# PIC32MX_circuit.net
KiCad netlist of a schematic drawn in Altium Designer
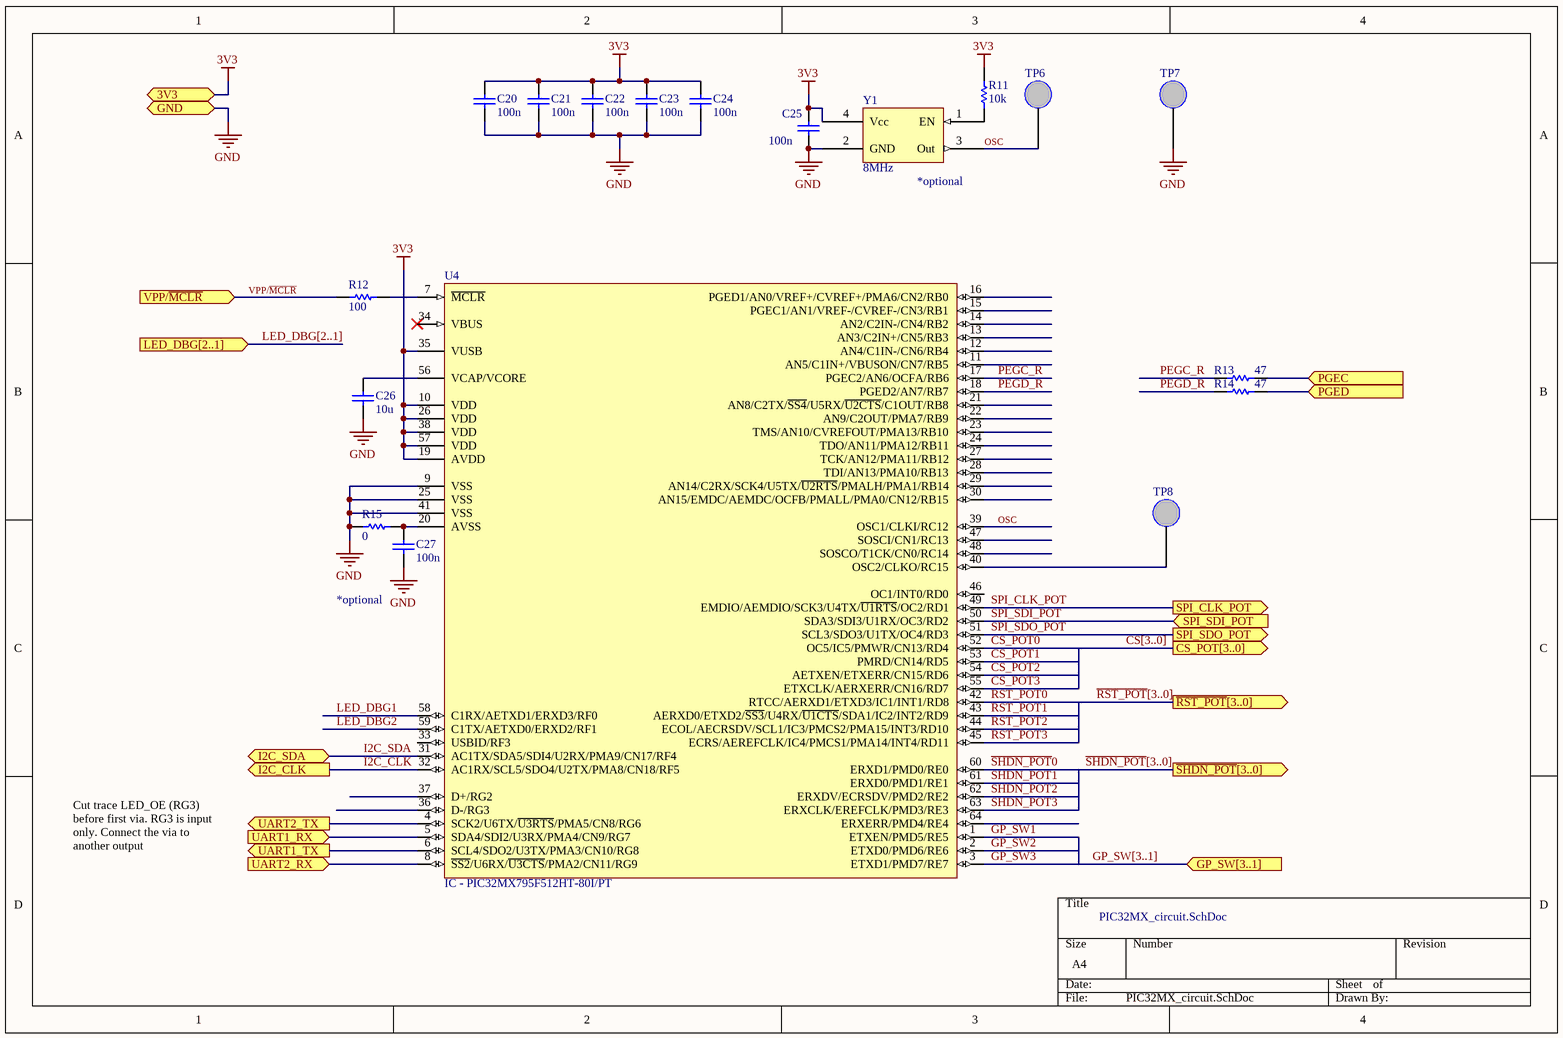
[diagram p0: PIC32MX_circuit.SchDoc]

(export (version "E")
  (design (tool "Eeschema 10.0.6"))
  (components
    (comp (ref "C20")
      (value "100n")
      (footprint "CS-0603")
      (fields
        (field (name "TOLERANCE") "10%")
        (field (name "VOLTAGE") "16V")
        (field (name "Comment") "CS - CAPACITOR")
      )
      (libsource (lib "CHINOOK_LIBRARY") (part "CS - CAPACITOR"))
    )
    (comp (ref "C21")
      (value "100n")
      (footprint "CS-0603")
      (fields
        (field (name "TOLERANCE") "10%")
        (field (name "VOLTAGE") "16V")
        (field (name "Comment") "CS - CAPACITOR")
      )
      (libsource (lib "CHINOOK_LIBRARY") (part "CS - CAPACITOR"))
    )
    (comp (ref "C22")
      (value "100n")
      (footprint "CS-0603")
      (fields
        (field (name "TOLERANCE") "10%")
        (field (name "VOLTAGE") "16V")
        (field (name "Comment") "CS - CAPACITOR")
      )
      (libsource (lib "CHINOOK_LIBRARY") (part "CS - CAPACITOR"))
    )
    (comp (ref "C23")
      (value "100n")
      (footprint "CS-0603")
      (fields
        (field (name "TOLERANCE") "10%")
        (field (name "VOLTAGE") "16V")
        (field (name "Comment") "CS - CAPACITOR")
      )
      (libsource (lib "CHINOOK_LIBRARY") (part "CS - CAPACITOR"))
    )
    (comp (ref "C24")
      (value "100n")
      (footprint "CS-0603")
      (fields
        (field (name "TOLERANCE") "10%")
        (field (name "VOLTAGE") "16V")
        (field (name "Comment") "CS - CAPACITOR")
      )
      (libsource (lib "CHINOOK_LIBRARY") (part "CS - CAPACITOR"))
    )
    (comp (ref "C25")
      (value "100n")
      (footprint "CS-0603")
      (fields
        (field (name "TOLERANCE") "10%")
        (field (name "VOLTAGE") "16V")
        (field (name "Comment") "CS - CAPACITOR")
      )
      (libsource (lib "CHINOOK_LIBRARY") (part "CS - CAPACITOR"))
    )
    (comp (ref "C26")
      (value "10u")
      (footprint "CS-0603")
      (fields
        (field (name "TOLERANCE") "10%")
        (field (name "VOLTAGE") "16V")
        (field (name "Comment") "CS - CAPACITOR")
      )
      (libsource (lib "CHINOOK_LIBRARY") (part "CS - CAPACITOR"))
    )
    (comp (ref "C27")
      (value "100n")
      (footprint "CS-0603")
      (fields
        (field (name "TOLERANCE") "10%")
        (field (name "VOLTAGE") "16V")
        (field (name "Comment") "CS - CAPACITOR")
      )
      (libsource (lib "CHINOOK_LIBRARY") (part "CS - CAPACITOR"))
    )
    (comp (ref "R11")
      (value "10k")
      (footprint "RS-0603")
      (fields
        (field (name "TOLERANCE") "RES TOL")
        (field (name "POWER") "RES POWER")
        (field (name "Comment") "RS - RESISTOR")
      )
      (libsource (lib "CHINOOK_LIBRARY") (part "RS - RESISTOR"))
    )
    (comp (ref "R12")
      (value "100")
      (footprint "RS-0603")
      (fields
        (field (name "TOLERANCE") "RES TOL")
        (field (name "POWER") "RES POWER")
        (field (name "Comment") "RS - RESISTOR")
      )
      (libsource (lib "CHINOOK_LIBRARY") (part "RS - RESISTOR"))
    )
    (comp (ref "R13")
      (value "47")
      (footprint "RS-0603")
      (fields
        (field (name "TOLERANCE") "RES TOL")
        (field (name "POWER") "RES POWER")
        (field (name "Comment") "RS - RESISTOR")
      )
      (libsource (lib "CHINOOK_LIBRARY") (part "RS - RESISTOR"))
    )
    (comp (ref "R14")
      (value "47")
      (footprint "RS-0603")
      (fields
        (field (name "TOLERANCE") "RES TOL")
        (field (name "POWER") "RES POWER")
        (field (name "Comment") "RS - RESISTOR")
      )
      (libsource (lib "CHINOOK_LIBRARY") (part "RS - RESISTOR"))
    )
    (comp (ref "R15")
      (value "0")
      (footprint "RS-0603")
      (fields
        (field (name "TOLERANCE") "RES TOL")
        (field (name "POWER") "RES POWER")
        (field (name "Comment") "RS - RESISTOR")
      )
      (libsource (lib "CHINOOK_LIBRARY") (part "RS - RESISTOR"))
    )
    (comp (ref "TP6")
      (value "5003K")
      (footprint "TP - VERTICAL")
      (libsource (lib "CHINOOK_LIBRARY") (part "TP - Test point vertical"))
    )
    (comp (ref "TP7")
      (value "5003K")
      (footprint "TP - VERTICAL")
      (libsource (lib "CHINOOK_LIBRARY") (part "TP - Test point vertical"))
    )
    (comp (ref "TP8")
      (value "5003K")
      (footprint "TP - VERTICAL")
      (libsource (lib "CHINOOK_LIBRARY") (part "TP - Test point vertical"))
    )
    (comp (ref "U4")
      (value "IC - PIC32MX795F512HT-80I/PT")
      (footprint "IC-TQFP-64")
      (fields (field (name "MANUFACTURER") "Microchip"))
      (libsource (lib "CHINOOK_LIBRARY") (part "IC - PIC32MX795F512HT-80I/PT"))
    )
    (comp (ref "Y1")
      (value "8MHz")
      (footprint "OSC-CB3LV")
      (description "Oscillator")
      (libsource (lib "CHINOOK_LIBRARY") (part "OSC - CB3LV"))
    )
  )
  (nets
    (net (code "5") (name "/CS0") (class "Default")
      (node (ref "U4") (pin "52") (pinfunction "OC5/IC5/PMWR/CN13/RD4_52") (pintype "bidirectional"))
    )
    (net (code "6") (name "/CS1") (class "Default")
      (node (ref "U4") (pin "53") (pinfunction "PMRD/CN14/RD5_53") (pintype "bidirectional"))
    )
    (net (code "7") (name "/CS2") (class "Default")
      (node (ref "U4") (pin "54") (pinfunction "AETXEN/ETXERR/CN15/RD6_54") (pintype "bidirectional"))
    )
    (net (code "8") (name "/CS3") (class "Default")
      (node (ref "U4") (pin "55") (pinfunction "ETXCLK/AERXERR/CN16/RD7_55") (pintype "bidirectional"))
    )
    (net (code "10") (name "/GP_SW1") (class "Default")
      (node (ref "U4") (pin "1") (pinfunction "ETXEN/PMD5/RE5_1") (pintype "bidirectional"))
    )
    (net (code "11") (name "/GP_SW2") (class "Default")
      (node (ref "U4") (pin "2") (pinfunction "ETXD0/PMD6/RE6_2") (pintype "bidirectional"))
    )
    (net (code "12") (name "/GP_SW3") (class "Default")
      (node (ref "U4") (pin "3") (pinfunction "ETXD1/PMD7/RE7_3") (pintype "bidirectional"))
    )
    (net (code "14") (name "/I2C_CLK") (class "Default")
      (node (ref "U4") (pin "32") (pinfunction "AC1RX/SCL5/SDO4/U2TX/PMA8/CN18/RF5_32") (pintype "bidirectional"))
    )
    (net (code "15") (name "/I2C_SDA") (class "Default")
      (node (ref "U4") (pin "31") (pinfunction "AC1TX/SDA5/SDI4/U2RX/PMA9/CN17/RF4_31") (pintype "bidirectional"))
    )
    (net (code "16") (name "/LED_DBG1") (class "Default")
      (node (ref "U4") (pin "58") (pinfunction "C1RX/AETXD1/ERXD3/RF0_58") (pintype "bidirectional"))
    )
    (net (code "17") (name "/LED_DBG2") (class "Default")
      (node (ref "U4") (pin "59") (pinfunction "C1TX/AETXD0/ERXD2/RF1_59") (pintype "bidirectional"))
    )
    (net (code "19") (name "/OSC") (class "Default")
      (node (ref "TP6") (pin "1") (pinfunction "1_1") (pintype "passive"))
      (node (ref "U4") (pin "39") (pinfunction "OSC1/CLKI/RC12_39") (pintype "bidirectional"))
      (node (ref "Y1") (pin "3") (pinfunction "Out_3") (pintype "output"))
    )
    (net (code "20") (name "/PEGC_R") (class "Default")
      (node (ref "R13") (pin "1") (pinfunction "1_1") (pintype "passive"))
      (node (ref "U4") (pin "17") (pinfunction "PGEC2/AN6/OCFA/RB6_17") (pintype "bidirectional"))
    )
    (net (code "21") (name "/PEGD_R") (class "Default")
      (node (ref "R14") (pin "1") (pinfunction "1_1") (pintype "passive"))
      (node (ref "U4") (pin "18") (pinfunction "PGED2/AN7/RB7_18") (pintype "bidirectional"))
    )
    (net (code "22") (name "/PGEC") (class "Default")
      (node (ref "R13") (pin "2") (pinfunction "2_2") (pintype "passive"))
    )
    (net (code "23") (name "/PGED") (class "Default")
      (node (ref "R14") (pin "2") (pinfunction "2_2") (pintype "passive"))
    )
    (net (code "24") (name "/SPI_CLK_POT") (class "Default")
      (node (ref "U4") (pin "49") (pinfunction "EMDIO/AEMDIO/SCK3/U4TX/~{U1RTS}/OC2/RD1_49") (pintype "bidirectional"))
    )
    (net (code "25") (name "/SPI_SDI_POT") (class "Default")
      (node (ref "U4") (pin "50") (pinfunction "SDA3/SDI3/U1RX/OC3/RD2_50") (pintype "bidirectional"))
    )
    (net (code "26") (name "/SPI_SDO_POT") (class "Default")
      (node (ref "U4") (pin "51") (pinfunction "SCL3/SDO3/U1TX/OC4/RD3_51") (pintype "bidirectional"))
    )
    (net (code "27") (name "/UART1_RX") (class "Default")
      (node (ref "U4") (pin "5") (pinfunction "SDA4/SDI2/U3RX/PMA4/CN9/RG7_5") (pintype "bidirectional"))
    )
    (net (code "28") (name "/UART1_TX") (class "Default")
      (node (ref "U4") (pin "6") (pinfunction "SCL4/SDO2/U3TX/PMA3/CN10/RG8_6") (pintype "bidirectional"))
    )
    (net (code "29") (name "/UART2_RX") (class "Default")
      (node (ref "U4") (pin "8") (pinfunction "~{SS2}/U6RX/~{U3CTS}/PMA2/CN11/RG9_8") (pintype "bidirectional"))
    )
    (net (code "30") (name "/UART2_TX") (class "Default")
      (node (ref "U4") (pin "4") (pinfunction "SCK2/U6TX/~{U3RTS}/PMA5/CN8/RG6_4") (pintype "bidirectional"))
    )
    (net (code "31") (name "/VPP{slash}~{MCLR}") (class "Default")
      (node (ref "R12") (pin "2") (pinfunction "2_2") (pintype "passive"))
    )
    (net (code "32") (name "/~{RST_POT}0") (class "Default")
      (node (ref "U4") (pin "42") (pinfunction "RTCC/AERXD1/ETXD3/IC1/INT1/RD8_42") (pintype "bidirectional"))
    )
    (net (code "33") (name "/~{RST_POT}1") (class "Default")
      (node (ref "U4") (pin "43") (pinfunction "AERXD0/ETXD2/~{SS3}/U4RX/~{U1CTS}/SDA1/IC2/INT2/RD9_43") (pintype "bidirectional"))
    )
    (net (code "34") (name "/~{RST_POT}2") (class "Default")
      (node (ref "U4") (pin "44") (pinfunction "ECOL/AECRSDV/SCL1/IC3/PMCS2/PMA15/INT3/RD10_44") (pintype "bidirectional"))
    )
    (net (code "35") (name "/~{RST_POT}3") (class "Default")
      (node (ref "U4") (pin "45") (pinfunction "ECRS/AEREFCLK/IC4/PMCS1/PMA14/INT4/RD11_45") (pintype "bidirectional"))
    )
    (net (code "37") (name "/~{SHDN_POT}0") (class "Default")
      (node (ref "U4") (pin "60") (pinfunction "ERXD1/PMD0/RE0_60") (pintype "bidirectional"))
    )
    (net (code "38") (name "/~{SHDN_POT}1") (class "Default")
      (node (ref "U4") (pin "61") (pinfunction "ERXD0/PMD1/RE1_61") (pintype "bidirectional"))
    )
    (net (code "39") (name "/~{SHDN_POT}2") (class "Default")
      (node (ref "U4") (pin "62") (pinfunction "ERXDV/ECRSDV/PMD2/RE2_62") (pintype "bidirectional"))
    )
    (net (code "40") (name "/~{SHDN_POT}3") (class "Default")
      (node (ref "U4") (pin "63") (pinfunction "ERXCLK/EREFCLK/PMD3/RE3_63") (pintype "bidirectional"))
    )
    (net (code "42") (name "3V3") (class "Default")
      (node (ref "C20") (pin "2") (pinfunction "2_2") (pintype "passive"))
      (node (ref "C21") (pin "2") (pinfunction "2_2") (pintype "passive"))
      (node (ref "C22") (pin "2") (pinfunction "2_2") (pintype "passive"))
      (node (ref "C23") (pin "2") (pinfunction "2_2") (pintype "passive"))
      (node (ref "C24") (pin "2") (pinfunction "2_2") (pintype "passive"))
      (node (ref "C25") (pin "2") (pinfunction "2_2") (pintype "passive"))
      (node (ref "R11") (pin "1") (pinfunction "1_1") (pintype "passive"))
      (node (ref "U4") (pin "10") (pinfunction "VDD_10") (pintype "power_in"))
      (node (ref "U4") (pin "19") (pinfunction "AVDD_19") (pintype "power_in"))
      (node (ref "U4") (pin "26") (pinfunction "VDD_26") (pintype "power_in"))
      (node (ref "U4") (pin "35") (pinfunction "VUSB_35") (pintype "power_in"))
      (node (ref "U4") (pin "38") (pinfunction "VDD_38") (pintype "power_in"))
      (node (ref "U4") (pin "57") (pinfunction "VDD_57") (pintype "power_in"))
      (node (ref "Y1") (pin "4") (pinfunction "Vcc_4") (pintype "power_in"))
    )
    (net (code "43") (name "GND") (class "Default")
      (node (ref "C20") (pin "1") (pinfunction "1_1") (pintype "passive"))
      (node (ref "C21") (pin "1") (pinfunction "1_1") (pintype "passive"))
      (node (ref "C22") (pin "1") (pinfunction "1_1") (pintype "passive"))
      (node (ref "C23") (pin "1") (pinfunction "1_1") (pintype "passive"))
      (node (ref "C24") (pin "1") (pinfunction "1_1") (pintype "passive"))
      (node (ref "C25") (pin "1") (pinfunction "1_1") (pintype "passive"))
      (node (ref "C26") (pin "1") (pinfunction "1_1") (pintype "passive"))
      (node (ref "C27") (pin "1") (pinfunction "1_1") (pintype "passive"))
      (node (ref "R15") (pin "2") (pinfunction "2_2") (pintype "passive"))
      (node (ref "TP7") (pin "1") (pinfunction "1_1") (pintype "passive"))
      (node (ref "U4") (pin "25") (pinfunction "VSS_25") (pintype "power_in"))
      (node (ref "U4") (pin "41") (pinfunction "VSS_41") (pintype "power_in"))
      (node (ref "U4") (pin "9") (pinfunction "VSS_9") (pintype "power_in"))
      (node (ref "Y1") (pin "2") (pinfunction "GND_2") (pintype "power_in"))
    )
    (net (code "44") (name "Net-(U4-AVSS)") (class "Default")
      (node (ref "C27") (pin "2") (pinfunction "2_2") (pintype "passive"))
      (node (ref "R15") (pin "1") (pinfunction "1_1") (pintype "passive"))
      (node (ref "U4") (pin "20") (pinfunction "AVSS_20") (pintype "power_in"))
    )
    (net (code "45") (name "Net-(U4-OSC2{slash}CLKO{slash}RC15)") (class "Default")
      (node (ref "TP8") (pin "1") (pinfunction "1_1") (pintype "passive"))
      (node (ref "U4") (pin "40") (pinfunction "OSC2/CLKO/RC15_40") (pintype "bidirectional"))
    )
    (net (code "46") (name "Net-(U4-VCAP{slash}VCORE)") (class "Default")
      (node (ref "C26") (pin "2") (pinfunction "2_2") (pintype "passive"))
      (node (ref "U4") (pin "56") (pinfunction "VCAP/VCORE_56") (pintype "power_in"))
    )
    (net (code "47") (name "Net-(U4-~{MCLR})") (class "Default")
      (node (ref "R12") (pin "1") (pinfunction "1_1") (pintype "passive"))
      (node (ref "U4") (pin "7") (pinfunction "~{MCLR}_7") (pintype "input"))
    )
    (net (code "48") (name "Net-(Y1-EN)") (class "Default")
      (node (ref "R11") (pin "2") (pinfunction "2_2") (pintype "passive"))
      (node (ref "Y1") (pin "1") (pinfunction "EN_1") (pintype "input"))
    )
    (net (code "49") (name "unconnected-(U4-AN2{slash}C2IN-{slash}CN4{slash}RB2-Pad14)") (class "Default")
      (node (ref "U4") (pin "14") (pinfunction "AN2/C2IN-/CN4/RB2_14") (pintype "bidirectional"))
    )
    (net (code "50") (name "unconnected-(U4-AN3{slash}C2IN+{slash}CN5{slash}RB3-Pad13)") (class "Default")
      (node (ref "U4") (pin "13") (pinfunction "AN3/C2IN+/CN5/RB3_13") (pintype "bidirectional"))
    )
    (net (code "51") (name "unconnected-(U4-AN4{slash}C1IN-{slash}CN6{slash}RB4-Pad12)") (class "Default")
      (node (ref "U4") (pin "12") (pinfunction "AN4/C1IN-/CN6/RB4_12") (pintype "bidirectional"))
    )
    (net (code "52") (name "unconnected-(U4-AN5{slash}C1IN+{slash}VBUSON{slash}CN7{slash}RB5-Pad11)") (class "Default")
      (node (ref "U4") (pin "11") (pinfunction "AN5/C1IN+/VBUSON/CN7/RB5_11") (pintype "bidirectional"))
    )
    (net (code "53") (name "unconnected-(U4-AN8{slash}C2TX{slash}~{SS4}{slash}U5RX{slash}~{U2CTS}{slash}C1OUT{slash}RB8-Pad21)") (class "Default")
      (node (ref "U4") (pin "21") (pinfunction "AN8/C2TX/~{SS4}/U5RX/~{U2CTS}/C1OUT/RB8_21") (pintype "bidirectional"))
    )
    (net (code "54") (name "unconnected-(U4-AN9{slash}C2OUT{slash}PMA7{slash}RB9-Pad22)") (class "Default")
      (node (ref "U4") (pin "22") (pinfunction "AN9/C2OUT/PMA7/RB9_22") (pintype "bidirectional"))
    )
    (net (code "55") (name "unconnected-(U4-AN14{slash}C2RX{slash}SCK4{slash}U5TX{slash}~{U2RTS}{slash}PMALH{slash}PMA1{slash}RB14-Pad29)") (class "Default")
      (node (ref "U4") (pin "29") (pinfunction "AN14/C2RX/SCK4/U5TX/~{U2RTS}/PMALH/PMA1/RB14_29") (pintype "bidirectional"))
    )
    (net (code "56") (name "unconnected-(U4-AN15{slash}EMDC{slash}AEMDC{slash}OCFB{slash}PMALL{slash}PMA0{slash}CN12{slash}RB15-Pad30)") (class "Default")
      (node (ref "U4") (pin "30") (pinfunction "AN15/EMDC/AEMDC/OCFB/PMALL/PMA0/CN12/RB15_30") (pintype "bidirectional"))
    )
    (net (code "57") (name "unconnected-(U4-D+{slash}RG2-Pad37)") (class "Default")
      (node (ref "U4") (pin "37") (pinfunction "D+/RG2_37") (pintype "bidirectional"))
    )
    (net (code "58") (name "unconnected-(U4-D-{slash}RG3-Pad36)") (class "Default")
      (node (ref "U4") (pin "36") (pinfunction "D-/RG3_36") (pintype "bidirectional"))
    )
    (net (code "59") (name "unconnected-(U4-ERXERR{slash}PMD4{slash}RE4-Pad64)") (class "Default")
      (node (ref "U4") (pin "64") (pinfunction "ERXERR/PMD4/RE4_64") (pintype "bidirectional"))
    )
    (net (code "60") (name "unconnected-(U4-OC1{slash}INT0{slash}RD0-Pad46)") (class "Default")
      (node (ref "U4") (pin "46") (pinfunction "OC1/INT0/RD0_46") (pintype "bidirectional"))
    )
    (net (code "61") (name "unconnected-(U4-PGEC1{slash}AN1{slash}VREF-{slash}CVREF-{slash}CN3{slash}RB1-Pad15)") (class "Default")
      (node (ref "U4") (pin "15") (pinfunction "PGEC1/AN1/VREF-/CVREF-/CN3/RB1_15") (pintype "bidirectional"))
    )
    (net (code "62") (name "unconnected-(U4-PGED1{slash}AN0{slash}VREF+{slash}CVREF+{slash}PMA6{slash}CN2{slash}RB0-Pad16)") (class "Default")
      (node (ref "U4") (pin "16") (pinfunction "PGED1/AN0/VREF+/CVREF+/PMA6/CN2/RB0_16") (pintype "bidirectional"))
    )
    (net (code "63") (name "unconnected-(U4-SOSCI{slash}CN1{slash}RC13-Pad47)") (class "Default")
      (node (ref "U4") (pin "47") (pinfunction "SOSCI/CN1/RC13_47") (pintype "bidirectional"))
    )
    (net (code "64") (name "unconnected-(U4-SOSCO{slash}T1CK{slash}CN0{slash}RC14-Pad48)") (class "Default")
      (node (ref "U4") (pin "48") (pinfunction "SOSCO/T1CK/CN0/RC14_48") (pintype "bidirectional"))
    )
    (net (code "65") (name "unconnected-(U4-TCK{slash}AN12{slash}PMA11{slash}RB12-Pad27)") (class "Default")
      (node (ref "U4") (pin "27") (pinfunction "TCK/AN12/PMA11/RB12_27") (pintype "bidirectional"))
    )
    (net (code "66") (name "unconnected-(U4-TDI{slash}AN13{slash}PMA10{slash}RB13-Pad28)") (class "Default")
      (node (ref "U4") (pin "28") (pinfunction "TDI/AN13/PMA10/RB13_28") (pintype "bidirectional"))
    )
    (net (code "67") (name "unconnected-(U4-TDO{slash}AN11{slash}PMA12{slash}RB11-Pad24)") (class "Default")
      (node (ref "U4") (pin "24") (pinfunction "TDO/AN11/PMA12/RB11_24") (pintype "bidirectional"))
    )
    (net (code "68") (name "unconnected-(U4-TMS{slash}AN10{slash}CVREFOUT{slash}PMA13{slash}RB10-Pad23)") (class "Default")
      (node (ref "U4") (pin "23") (pinfunction "TMS/AN10/CVREFOUT/PMA13/RB10_23") (pintype "bidirectional"))
    )
    (net (code "69") (name "unconnected-(U4-USBID{slash}RF3-Pad33)") (class "Default")
      (node (ref "U4") (pin "33") (pinfunction "USBID/RF3_33") (pintype "bidirectional"))
    )
    (net (code "70") (name "unconnected-(U4-VBUS-Pad34)") (class "Default")
      (node (ref "U4") (pin "34") (pinfunction "VBUS_34") (pintype "input+no_connect"))
    )
  )
)
